# Own3V3BUCK.net
KiCad netlist of a schematic drawn in Altium Designer
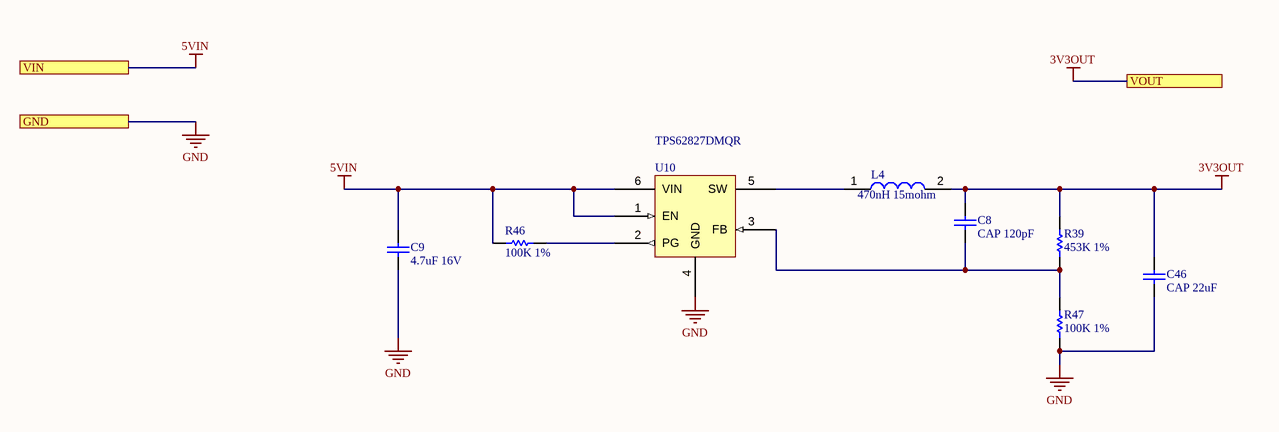
[diagram p0: Own3V3BUCK.SchDoc]

(export (version "E")
  (design (tool "Eeschema 10.0.6"))
  (components
    (comp (ref "C8")
      (value "CAP 120pF")
      (footprint "CAPC0603(1608)100_N")
      (description "CAP 120pF 10V ±1% 0603 (1608 Metric) Thickness 1mm SMD")
      (fields (field (name "TOLERANCE") "Â±1%"))
      (libsource (lib "Altium Content Vault") (part "CAP"))
    )
    (comp (ref "C9")
      (value "4.7uF 16V")
      (footprint "CAPC0805(2012)145_N")
      (description "CAP 4.7uF 16V -20% to +80% 0805 (2012 Metric) Thickness 1.45mm SMD")
      (fields (field (name "TOLERANCE") "-20% to +80%"))
      (libsource (lib "Altium Content Vault") (part "CAP"))
    )
    (comp (ref "C46")
      (value "CAP 22uF")
      (footprint "CAPC0805(2012)100_L")
      (description "CAP 22uF 10V ±20% 0805 (2012 Metric) Thickness 1mm SMD")
      (fields (field (name "TOLERANCE") "Â±20%"))
      (libsource (lib "Altium Content Vault") (part "CAP"))
    )
    (comp (ref "L4")
      (value "470nH 15mohm")
      (footprint "INDPM3630X150N")
      (description "Inductor Power Shielded Wirewound 470nH 20% 100KHz 6.7A 15mOhm DCR 1212 T/R")
      (fields
        (field (name "MANUFACTURER_PART_NUMBER") "IHLP1212AEERR47M11")
        (field (name "MOUSER PART NUMBER") "70-IHLP1212AEERR47M1")
      )
      (libsource (lib "buckinductor") (part "IHLP1212AEERR47M11"))
    )
    (comp (ref "R39")
      (value "453K 1%")
      (footprint "RESC0603(1608)_N")
      (description "453K 0.1W 1% 0603 (1608 Metric)  SMD")
      (fields (field (name "TOLERANCE") "1 %") (field (name "POWER") "0.1 W"))
      (libsource (lib "Altium Content Vault") (part "RES"))
    )
    (comp (ref "R46")
      (value "100K 1%")
      (footprint "RESC0603(1608)_N")
      (description "100K 0.1W 1% 0603 (1608 Metric)  SMD")
      (fields (field (name "POWER") "0.1 W") (field (name "TOLERANCE") "1 %"))
      (libsource (lib "Altium Content Vault") (part "RES"))
    )
    (comp (ref "R47")
      (value "100K 1%")
      (footprint "RESC0603(1608)_N")
      (description "100K 0.1W 1% 0603 (1608 Metric)  SMD")
      (fields (field (name "POWER") "0.1 W") (field (name "TOLERANCE") "1 %"))
      (libsource (lib "Altium Content Vault") (part "RES"))
    )
    (comp (ref "U10")
      (value "TPS62827DMQR")
      (footprint "TPS62827DMQR")
      (description "2.4V-5.5V input, 4A step-down converter with 1% Accuracy in 1.5mm x 1.5mm QFN 6-VSON-HR -40 to 125")
      (fields (field (name "MANUFACTURER") "Texas Instruments"))
      (libsource (lib "TPS62827DMQR") (part "TPS62827DMQR"))
    )
  )
  (nets
    (net (code "1") (name "3V3OUT") (class "Default")
      (node (ref "C46") (pin "2") (pinfunction "2_2") (pintype "passive"))
      (node (ref "C8") (pin "2") (pinfunction "2_2") (pintype "passive"))
      (node (ref "L4") (pin "2") (pinfunction "2_2") (pintype "passive"))
      (node (ref "R39") (pin "2") (pinfunction "2_2") (pintype "passive"))
    )
    (net (code "2") (name "5VIN") (class "Default")
      (node (ref "C9") (pin "2") (pinfunction "2_2") (pintype "passive"))
      (node (ref "R46") (pin "1") (pinfunction "1_1") (pintype "passive"))
      (node (ref "U10") (pin "1") (pinfunction "EN_1") (pintype "input"))
      (node (ref "U10") (pin "6") (pinfunction "VIN_6") (pintype "power_in"))
    )
    (net (code "3") (name "GND") (class "Default")
      (node (ref "C46") (pin "1") (pinfunction "1_1") (pintype "passive"))
      (node (ref "C9") (pin "1") (pinfunction "1_1") (pintype "passive"))
      (node (ref "R47") (pin "1") (pinfunction "1_1") (pintype "passive"))
      (node (ref "U10") (pin "4") (pinfunction "GND_4") (pintype "passive"))
    )
    (net (code "4") (name "Net-(U10-FB)") (class "Default")
      (node (ref "C8") (pin "1") (pinfunction "1_1") (pintype "passive"))
      (node (ref "R39") (pin "1") (pinfunction "1_1") (pintype "passive"))
      (node (ref "R47") (pin "2") (pinfunction "2_2") (pintype "passive"))
      (node (ref "U10") (pin "3") (pinfunction "FB_3") (pintype "input"))
    )
    (net (code "5") (name "Net-(U10-PG)") (class "Default")
      (node (ref "R46") (pin "2") (pinfunction "2_2") (pintype "passive"))
      (node (ref "U10") (pin "2") (pinfunction "PG_2") (pintype "output"))
    )
    (net (code "6") (name "Net-(U10-SW)") (class "Default")
      (node (ref "L4") (pin "1") (pinfunction "1_1") (pintype "passive"))
      (node (ref "U10") (pin "5") (pinfunction "SW_5") (pintype "power_in"))
    )
  )
)
